# design.net
KiCad netlist of a schematic drawn in Altium Designer
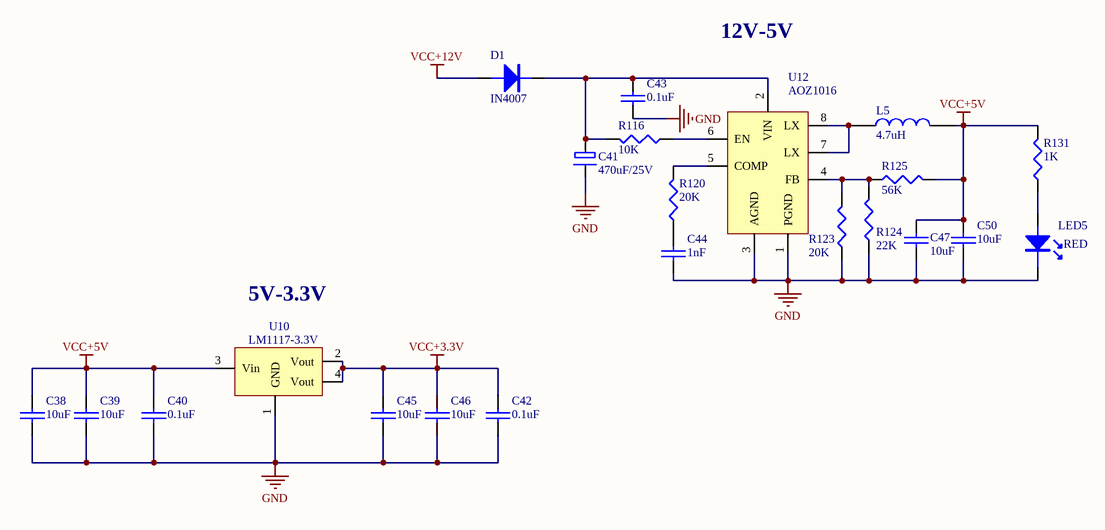
[diagram p0: 电源.SchDoc]

(export (version "E")
  (design (tool "Eeschema 10.0.6"))
  (components
    (comp (ref "C38")
      (value "10uF")
      (footprint "0805")
      (description "0805陶瓷贴片电容")
      (libsource (lib "INSPUR_PCB") (part "CAP-0805"))
    )
    (comp (ref "C39")
      (value "10uF")
      (footprint "0805")
      (description "0805陶瓷贴片电容")
      (libsource (lib "INSPUR_PCB") (part "CAP-0805"))
    )
    (comp (ref "C40")
      (value "0.1uF")
      (footprint "0603")
      (description "0603陶瓷贴片电容")
      (libsource (lib "INSPUR_PCB") (part "CAP-0603"))
    )
    (comp (ref "C41")
      (value "470uF/25V")
      (footprint "RB3.5")
      (description "470uF/25V电解电容")
      (libsource (lib "INSPUR_PCB") (part "470uF/25V"))
    )
    (comp (ref "C42")
      (value "0.1uF")
      (footprint "0603")
      (description "0603陶瓷贴片电容")
      (libsource (lib "INSPUR_PCB") (part "CAP-0603"))
    )
    (comp (ref "C43")
      (value "0.1uF")
      (footprint "0603")
      (description "0603陶瓷贴片电容")
      (libsource (lib "INSPUR_PCB") (part "CAP-0603"))
    )
    (comp (ref "C44")
      (value "1nF")
      (footprint "0603")
      (description "0603陶瓷贴片电容")
      (libsource (lib "INSPUR_PCB") (part "CAP-0603"))
    )
    (comp (ref "C45")
      (value "10uF")
      (footprint "0805")
      (description "0805陶瓷贴片电容")
      (libsource (lib "INSPUR_PCB") (part "CAP-0805"))
    )
    (comp (ref "C46")
      (value "10uF")
      (footprint "0805")
      (description "0805陶瓷贴片电容")
      (libsource (lib "INSPUR_PCB") (part "CAP-0805"))
    )
    (comp (ref "C47")
      (value "10uF")
      (footprint "0805")
      (description "0805陶瓷贴片电容")
      (libsource (lib "INSPUR_PCB") (part "CAP-0805"))
    )
    (comp (ref "C50")
      (value "10uF")
      (footprint "0805")
      (description "0805陶瓷贴片电容")
      (libsource (lib "INSPUR_PCB") (part "CAP-0805"))
    )
    (comp (ref "D1")
      (value "IN4007")
      (footprint "SMA(DO-214AC)")
      (description "整流二极管")
      (libsource (lib "INSPUR_PCB") (part "IN4007"))
    )
    (comp (ref "L5") (value "4.7uH") (footprint "INDUCTOR 7*7") (libsource (lib "mylib") (part "INDUCTOR")))
    (comp (ref "LED5")
      (value "RED")
      (footprint "LED-0603")
      (description "LED贴片发光二极管0603封装")
      (libsource (lib "INSPUR_PCB") (part "LED-0603"))
    )
    (comp (ref "R116")
      (value "10K")
      (footprint "0603")
      (description "陶瓷贴片电阻0603封装")
      (libsource (lib "INSPUR_PCB") (part "RES-0603"))
    )
    (comp (ref "R120")
      (value "20K")
      (footprint "0603")
      (description "陶瓷贴片电阻0603封装")
      (libsource (lib "INSPUR_PCB") (part "RES-0603"))
    )
    (comp (ref "R123")
      (value "20K")
      (footprint "0603")
      (description "陶瓷贴片电阻0603封装")
      (libsource (lib "INSPUR_PCB") (part "RES-0603"))
    )
    (comp (ref "R124")
      (value "22K")
      (footprint "0603")
      (description "陶瓷贴片电阻0603封装")
      (libsource (lib "INSPUR_PCB") (part "RES-0603"))
    )
    (comp (ref "R125")
      (value "56K")
      (footprint "0603")
      (description "陶瓷贴片电阻0603封装")
      (libsource (lib "INSPUR_PCB") (part "RES-0603"))
    )
    (comp (ref "R131")
      (value "1K")
      (footprint "0603")
      (description "陶瓷贴片电阻0603封装")
      (libsource (lib "INSPUR_PCB") (part "RES-0603"))
    )
    (comp (ref "U10")
      (value "LM1117-3.3V")
      (footprint "SOT-223")
      (libsource (lib "INSPUR_PCB") (part "LM1117-3.3V"))
    )
    (comp (ref "U12")
      (value "AOZ1016")
      (footprint "SO-8")
      (description "DC-DC降压电源管理芯片")
      (libsource (lib "INSPUR_PCB") (part "AOZ1016"))
    )
  )
  (nets
    (net (code "2") (name "GND") (class "Default")
      (node (ref "C38") (pin "2") (pinfunction "2_2") (pintype "passive"))
      (node (ref "C39") (pin "2") (pinfunction "2_2") (pintype "passive"))
      (node (ref "C40") (pin "1") (pinfunction "1_1") (pintype "passive"))
      (node (ref "C41") (pin "2") (pintype "passive"))
      (node (ref "C42") (pin "1") (pinfunction "1_1") (pintype "passive"))
      (node (ref "C43") (pin "1") (pinfunction "1_1") (pintype "passive"))
      (node (ref "C44") (pin "1") (pinfunction "1_1") (pintype "passive"))
      (node (ref "C45") (pin "2") (pinfunction "2_2") (pintype "passive"))
      (node (ref "C46") (pin "2") (pinfunction "2_2") (pintype "passive"))
      (node (ref "C47") (pin "1") (pinfunction "1_1") (pintype "passive"))
      (node (ref "C50") (pin "2") (pinfunction "2_2") (pintype "passive"))
      (node (ref "LED5") (pin "2") (pinfunction "2_2") (pintype "passive"))
      (node (ref "R123") (pin "1") (pinfunction "1_1") (pintype "passive"))
      (node (ref "R124") (pin "1") (pinfunction "1_1") (pintype "passive"))
      (node (ref "U10") (pin "1") (pinfunction "GND_1") (pintype "passive"))
      (node (ref "U12") (pin "1") (pinfunction "PGND_1") (pintype "passive"))
      (node (ref "U12") (pin "3") (pinfunction "AGND_3") (pintype "passive"))
    )
    (net (code "3") (name "Net-(C44-Pad2)") (class "Default")
      (node (ref "C44") (pin "2") (pinfunction "2_2") (pintype "passive"))
      (node (ref "R120") (pin "1") (pinfunction "1_1") (pintype "passive"))
    )
    (net (code "4") (name "Net-(D1-K)") (class "Default")
      (node (ref "C41") (pin "1") (pintype "passive"))
      (node (ref "C43") (pin "2") (pinfunction "2_2") (pintype "passive"))
      (node (ref "D1") (pin "2") (pinfunction "K_2") (pintype "passive"))
      (node (ref "R116") (pin "2") (pinfunction "2_2") (pintype "passive"))
      (node (ref "U12") (pin "2") (pinfunction "VIN_2") (pintype "passive"))
    )
    (net (code "5") (name "Net-(L5-Pad1)") (class "Default")
      (node (ref "L5") (pin "1") (pinfunction "1_1") (pintype "passive"))
      (node (ref "U12") (pin "7") (pinfunction "LX_7") (pintype "passive"))
      (node (ref "U12") (pin "8") (pinfunction "LX_8") (pintype "passive"))
    )
    (net (code "6") (name "Net-(LED5-Pad1)") (class "Default")
      (node (ref "LED5") (pin "1") (pinfunction "1_1") (pintype "passive"))
      (node (ref "R131") (pin "1") (pinfunction "1_1") (pintype "passive"))
    )
    (net (code "7") (name "Net-(U12-COMP)") (class "Default")
      (node (ref "R120") (pin "2") (pinfunction "2_2") (pintype "passive"))
      (node (ref "U12") (pin "5") (pinfunction "COMP_5") (pintype "passive"))
    )
    (net (code "8") (name "Net-(U12-EN)") (class "Default")
      (node (ref "R116") (pin "1") (pinfunction "1_1") (pintype "passive"))
      (node (ref "U12") (pin "6") (pinfunction "EN_6") (pintype "passive"))
    )
    (net (code "9") (name "Net-(U12-FB)") (class "Default")
      (node (ref "R123") (pin "2") (pinfunction "2_2") (pintype "passive"))
      (node (ref "R124") (pin "2") (pinfunction "2_2") (pintype "passive"))
      (node (ref "R125") (pin "1") (pinfunction "1_1") (pintype "passive"))
      (node (ref "U12") (pin "4") (pinfunction "FB_4") (pintype "passive"))
    )
    (net (code "10") (name "VCC+3.3V") (class "Default")
      (node (ref "C42") (pin "2") (pinfunction "2_2") (pintype "passive"))
      (node (ref "C45") (pin "1") (pinfunction "1_1") (pintype "passive"))
      (node (ref "C46") (pin "1") (pinfunction "1_1") (pintype "passive"))
      (node (ref "U10") (pin "2") (pinfunction "Vout_2") (pintype "passive"))
      (node (ref "U10") (pin "4") (pinfunction "Vout_4") (pintype "passive"))
    )
    (net (code "11") (name "VCC+5V") (class "Default")
      (node (ref "C38") (pin "1") (pinfunction "1_1") (pintype "passive"))
      (node (ref "C39") (pin "1") (pinfunction "1_1") (pintype "passive"))
      (node (ref "C40") (pin "2") (pinfunction "2_2") (pintype "passive"))
      (node (ref "C47") (pin "2") (pinfunction "2_2") (pintype "passive"))
      (node (ref "C50") (pin "1") (pinfunction "1_1") (pintype "passive"))
      (node (ref "L5") (pin "2") (pinfunction "2_2") (pintype "passive"))
      (node (ref "R125") (pin "2") (pinfunction "2_2") (pintype "passive"))
      (node (ref "R131") (pin "2") (pinfunction "2_2") (pintype "passive"))
      (node (ref "U10") (pin "3") (pinfunction "Vin_3") (pintype "passive"))
    )
    (net (code "12") (name "VCC+12V") (class "Default")
      (node (ref "D1") (pin "1") (pinfunction "A_1") (pintype "passive"))
    )
  )
)
